# Sheet2.net
KiCad netlist of a schematic drawn in Altium Designer
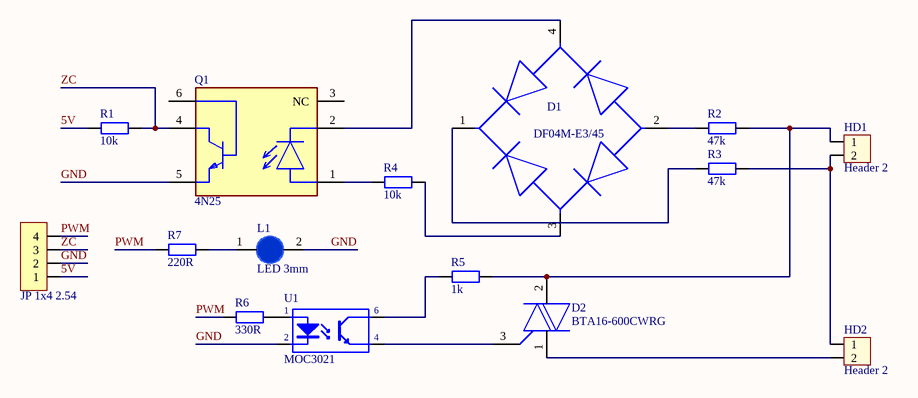
[diagram p0: Sheet2.SchDoc]

(export (version "E")
  (design (tool "Eeschema 10.0.6"))
  (components
    (comp (ref "D1")
      (value "DF04M-E3/45")
      (footprint "FP-DF04M-E3-45-0")
      (libsource (lib "Components - 01.04.24 - 23.18") (part "CMP-00030-42173530-1"))
    )
    (comp (ref "D2")
      (value "BTA16-600CWRG")
      (footprint "FP-TO-220AB_Ins-MFG")
      (description "TRIAC ALTERNISTOR 600V TO220AB")
      (fields
        (field (name "OCTOPART") "https://octopart.com/bta16-600cwrg-stmicroelectronics-360233")
        (field (name "MANUFACTURER") "STMicroelectronics")
      )
      (libsource (lib "Components - 01.04.24 - 23.26") (part "CMP-12193-000001-1"))
    )
    (comp (ref "HD1")
      (value "Header 2")
      (footprint "HED2")
      (description "Header 2 (Green)")
      (libsource (lib "syhaunguyen") (part "Hed2"))
    )
    (comp (ref "HD2")
      (value "Header 2")
      (footprint "HED2")
      (description "Header 2 (Green)")
      (libsource (lib "syhaunguyen") (part "Hed2"))
    )
    (comp (ref "JP1")
      (value "JP 1x4 2.54")
      (footprint "JP 1x4 DT")
      (description "Cắm")
      (libsource (lib "Altium_Lib_by_KhueNguyenCreator") (part "JP 1x4 2.54 Duc Thang"))
    )
    (comp (ref "L1")
      (value "LED 3mm")
      (footprint "LED-3MM-BLUE")
      (description "Cắm")
      (libsource (lib "Altium_Lib_by_KhueNguyenCreator") (part "LED 3mm Xanh Duong"))
    )
    (comp (ref "Q1")
      (value "4N25")
      (footprint "FP-4N25-MFG")
      (description "OPTOISO 2.5KV TRANS W/BASE 6DIP")
      (libsource (lib "4N25") (part "CMP-22018-000009-1"))
    )
    (comp (ref "R1")
      (value "10k")
      (footprint "tro vach 1/4w")
      (description "Cắm")
      (libsource (lib "Altium_Lib_by_KhueNguyenCreator") (part "Tro Vach 1/4W 1% 10k"))
    )
    (comp (ref "R2")
      (value "47k")
      (footprint "tro vach 1/4w")
      (description "Cắm")
      (libsource (lib "Altium_Lib_by_KhueNguyenCreator") (part "Tro Vach 1/4W 5% 47k"))
    )
    (comp (ref "R3")
      (value "47k")
      (footprint "tro vach 1/4w")
      (description "Cắm")
      (libsource (lib "Altium_Lib_by_KhueNguyenCreator") (part "Tro Vach 1/4W 5% 47k"))
    )
    (comp (ref "R4")
      (value "10k")
      (footprint "tro vach 1/4w")
      (description "Cắm")
      (libsource (lib "Altium_Lib_by_KhueNguyenCreator") (part "Tro Vach 1/4W 1% 10k"))
    )
    (comp (ref "R5")
      (value "1k")
      (footprint "tro vach 1/4w")
      (description "Cắm")
      (libsource (lib "Altium_Lib_by_KhueNguyenCreator") (part "Tro Vach 1/4W 5% 1k"))
    )
    (comp (ref "R6")
      (value "330R")
      (footprint "tro vach 1/4w")
      (description "Cắm")
      (libsource (lib "Altium_Lib_by_KhueNguyenCreator") (part "Tro Vach 1/4W 1% 330R"))
    )
    (comp (ref "R7")
      (value "220R")
      (footprint "tro vach 1/4w")
      (description "Cắm")
      (libsource (lib "Altium_Lib_by_KhueNguyenCreator") (part "Tro Vach 1/4W 5% 220R"))
    )
    (comp (ref "U1")
      (value "MOC3021")
      (footprint "DIP6/W0.3")
      (description "Single Opto")
      (libsource (lib "Library AL") (part "MOC3021"))
    )
  )
  (nets
    (net (code "1") (name "/5V") (class "Default")
      (node (ref "JP1") (pin "1") (pinfunction "1_1") (pintype "passive"))
      (node (ref "R1") (pin "1") (pinfunction "1_1") (pintype "passive"))
    )
    (net (code "2") (name "/GND") (class "Default")
      (node (ref "JP1") (pin "2") (pinfunction "2_2") (pintype "passive"))
      (node (ref "L1") (pin "2") (pinfunction "K_2") (pintype "passive"))
      (node (ref "Q1") (pin "5") (pinfunction "C_5") (pintype "passive"))
      (node (ref "U1") (pin "2") (pinfunction "K_2") (pintype "passive"))
    )
    (net (code "3") (name "/PWM") (class "Default")
      (node (ref "JP1") (pin "4") (pinfunction "4_4") (pintype "passive"))
      (node (ref "R6") (pin "1") (pinfunction "1_1") (pintype "passive"))
      (node (ref "R7") (pin "1") (pinfunction "1_1") (pintype "passive"))
    )
    (net (code "4") (name "/ZC") (class "Default")
      (node (ref "JP1") (pin "3") (pinfunction "3_3") (pintype "passive"))
      (node (ref "Q1") (pin "4") (pinfunction "E_4") (pintype "passive"))
      (node (ref "R1") (pin "2") (pinfunction "2_2") (pintype "passive"))
    )
    (net (code "5") (name "Net-(D1-+)") (class "Default")
      (node (ref "D1") (pin "1") (pinfunction "+_1") (pintype "passive"))
      (node (ref "R3") (pin "1") (pinfunction "1_1") (pintype "passive"))
    )
    (net (code "6") (name "Net-(D1--)") (class "Default")
      (node (ref "D1") (pin "2") (pinfunction "-_2") (pintype "passive"))
      (node (ref "R2") (pin "1") (pinfunction "1_1") (pintype "passive"))
    )
    (net (code "7") (name "Net-(D1-1_~)") (class "Default")
      (node (ref "D1") (pin "3") (pinfunction "1_~_3") (pintype "passive"))
      (node (ref "R4") (pin "2") (pinfunction "2_2") (pintype "passive"))
    )
    (net (code "8") (name "Net-(D1-2_~)") (class "Default")
      (node (ref "D1") (pin "4") (pinfunction "2_~_4") (pintype "passive"))
      (node (ref "Q1") (pin "2") (pinfunction "C_2") (pintype "passive"))
    )
    (net (code "9") (name "Net-(D2-A1)") (class "Default")
      (node (ref "D2") (pin "1") (pinfunction "A1_1") (pintype "passive"))
      (node (ref "HD2") (pin "2") (pinfunction "2_2") (pintype "passive"))
    )
    (net (code "10") (name "Net-(D2-A2)") (class "Default")
      (node (ref "D2") (pin "2") (pinfunction "A2_2") (pintype "passive"))
      (node (ref "HD1") (pin "1") (pinfunction "1_1") (pintype "passive"))
      (node (ref "R2") (pin "2") (pinfunction "2_2") (pintype "passive"))
      (node (ref "R5") (pin "2") (pinfunction "2_2") (pintype "passive"))
    )
    (net (code "11") (name "Net-(D2-G)") (class "Default")
      (node (ref "D2") (pin "3") (pinfunction "G_3") (pintype "passive"))
      (node (ref "U1") (pin "4") (pinfunction "E_4") (pintype "passive"))
    )
    (net (code "12") (name "Net-(HD1-Pad2)") (class "Default")
      (node (ref "HD1") (pin "2") (pinfunction "2_2") (pintype "passive"))
      (node (ref "HD2") (pin "1") (pinfunction "1_1") (pintype "passive"))
      (node (ref "R3") (pin "2") (pinfunction "2_2") (pintype "passive"))
    )
    (net (code "13") (name "Net-(L1-A)") (class "Default")
      (node (ref "L1") (pin "1") (pinfunction "A_1") (pintype "passive"))
      (node (ref "R7") (pin "2") (pinfunction "2_2") (pintype "passive"))
    )
    (net (code "14") (name "Net-(Q1-A)") (class "Default")
      (node (ref "Q1") (pin "1") (pinfunction "A_1") (pintype "passive"))
      (node (ref "R4") (pin "1") (pinfunction "1_1") (pintype "passive"))
    )
    (net (code "15") (name "Net-(U1-A)") (class "Default")
      (node (ref "R6") (pin "2") (pinfunction "2_2") (pintype "passive"))
      (node (ref "U1") (pin "1") (pinfunction "A_1") (pintype "passive"))
    )
    (net (code "16") (name "Net-(U1-C)") (class "Default")
      (node (ref "R5") (pin "1") (pinfunction "1_1") (pintype "passive"))
      (node (ref "U1") (pin "6") (pinfunction "C_6") (pintype "passive"))
    )
    (net (code "17") (name "unconnected-(Q1-B-Pad6)") (class "Default")
      (node (ref "Q1") (pin "6") (pinfunction "B_6") (pintype "passive"))
    )
    (net (code "18") (name "unconnected-(Q1-NC-Pad3)") (class "Default")
      (node (ref "Q1") (pin "3") (pinfunction "NC_3") (pintype "passive"))
    )
  )
)
